# RC_Transmitter_RX_FINAL_v4_4.net
KiCad netlist of a schematic drawn in EAGLE
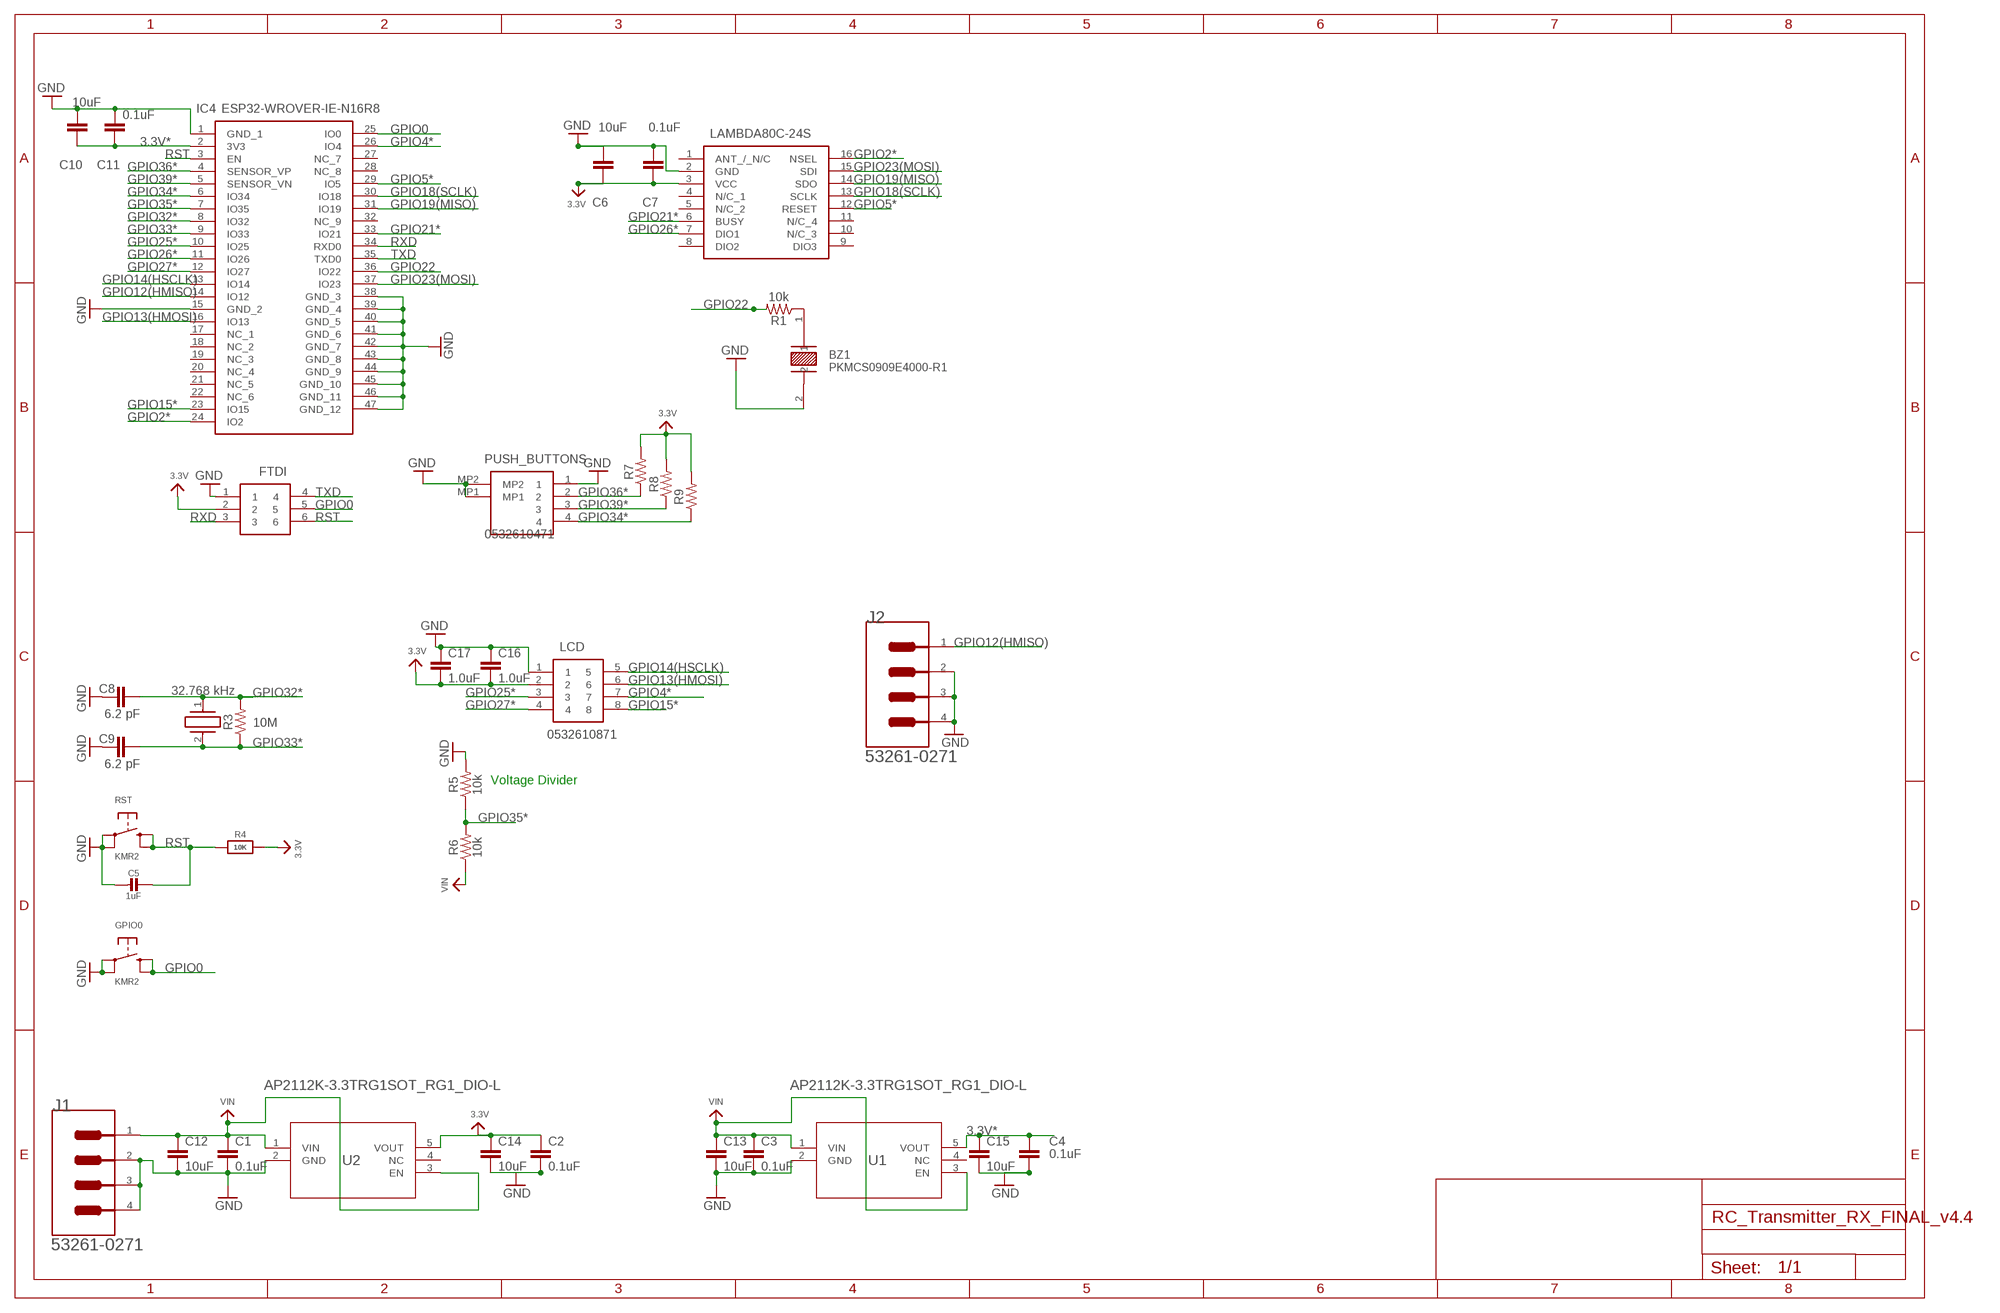
[diagram p0: schematic, sheet 1]

(export (version "E")
  (design (tool "Eeschema 10.0.6"))
  (components
    (comp (ref "BZ1")
      (value "PKMCS0909E4000-R1")
      (footprint "eagle-import:PKMCS0909E4000-R1")
      (fields
        (field (name "DIGIKEY_PARTNO") "490-9647-2-ND")
        (field (name "MANUFACTURER") "Murata Electronics")
        (field (name "CREATED_BY") " PCBLayout.com")
      )
      (libsource (lib "eagle-import") (part "PKMCS0909E4000-R1"))
    )
    (comp (ref "C1")
      (value "0.1uF")
      (footprint "eagle-import:0805")
      (libsource (lib "eagle-import") (part "10UF-0805-10V-10%"))
    )
    (comp (ref "C2")
      (value "0.1uF")
      (footprint "eagle-import:0805")
      (libsource (lib "eagle-import") (part "10UF-0805-10V-10%"))
    )
    (comp (ref "C3")
      (value "0.1uF")
      (footprint "eagle-import:0805")
      (libsource (lib "eagle-import") (part "10UF-0805-10V-10%"))
    )
    (comp (ref "C4")
      (value "0.1uF")
      (footprint "eagle-import:0805")
      (libsource (lib "eagle-import") (part "10UF-0805-10V-10%"))
    )
    (comp (ref "C5")
      (value "1uF")
      (footprint "eagle-import:0805-NO")
      (libsource (lib "eagle-import") (part "CAP_CERAMIC0805-NOOUTLINE"))
    )
    (comp (ref "C6")
      (value "10uF")
      (footprint "eagle-import:0805")
      (libsource (lib "eagle-import") (part "10UF-0805-10V-10%"))
    )
    (comp (ref "C7")
      (value "0.1uF")
      (footprint "eagle-import:0805")
      (libsource (lib "eagle-import") (part "10UF-0805-10V-10%"))
    )
    (comp (ref "C8")
      (value "6.2 pF")
      (footprint "eagle-import:CAPC2012X110")
      (libsource (lib "eagle-import") (part "CCHIP-0805(2012-METRIC)_"))
    )
    (comp (ref "C9")
      (value "6.2 pF")
      (footprint "eagle-import:CAPC2012X110")
      (libsource (lib "eagle-import") (part "CCHIP-0805(2012-METRIC)_"))
    )
    (comp (ref "C10")
      (value "10uF")
      (footprint "eagle-import:0805")
      (libsource (lib "eagle-import") (part "10UF-0805-10V-10%"))
    )
    (comp (ref "C11")
      (value "0.1uF")
      (footprint "eagle-import:0805")
      (libsource (lib "eagle-import") (part "10UF-0805-10V-10%"))
    )
    (comp (ref "C12")
      (value "10uF")
      (footprint "eagle-import:0805")
      (libsource (lib "eagle-import") (part "10UF-0805-10V-10%"))
    )
    (comp (ref "C13")
      (value "10uF")
      (footprint "eagle-import:0805")
      (libsource (lib "eagle-import") (part "10UF-0805-10V-10%"))
    )
    (comp (ref "C14")
      (value "10uF")
      (footprint "eagle-import:0805")
      (libsource (lib "eagle-import") (part "10UF-0805-10V-10%"))
    )
    (comp (ref "C15")
      (value "10uF")
      (footprint "eagle-import:0805")
      (libsource (lib "eagle-import") (part "10UF-0805-10V-10%"))
    )
    (comp (ref "C16")
      (value "1.0uF")
      (footprint "eagle-import:0805")
      (libsource (lib "eagle-import") (part "10UF-0805-10V-10%"))
    )
    (comp (ref "C17")
      (value "1.0uF")
      (footprint "eagle-import:0805")
      (libsource (lib "eagle-import") (part "10UF-0805-10V-10%"))
    )
    (comp (ref "CRYSTAL")
      (value "32.768 kHz")
      (footprint "eagle-import:ECX327CDX1293")
      (fields
        (field (name "ARROW_PART_NUMBER") "ECX-.327-CDX-1293")
        (field (name "MOUSER_PART_NUMBER") "520-ECX-.327CDX-1293")
        (field (name "ARROW_PART_NUMBER_1") "Crystal")
      )
      (libsource (lib "eagle-import") (part "ECX-.327-CDX-1293"))
    )
    (comp (ref "FTDI")
      (value "0532610671")
      (footprint "eagle-import:0532610671")
      (libsource (lib "eagle-import") (part "0532610671"))
    )
    (comp (ref "GPIO0")
      (value "KMR2")
      (footprint "eagle-import:BTN_KMR2_4.6X2.8")
      (libsource (lib "eagle-import") (part "SWITCH_TACT_SMT4.6X2.8"))
    )
    (comp (ref "IC1")
      (value "LAMBDA80C-24S")
      (footprint "eagle-import:LAMBDA80C24S")
      (fields (field (name "MOUSER_PART_NUMBER") "223-LAMBDA80C-24S"))
      (libsource (lib "eagle-import") (part "LAMBDA80C-24S"))
    )
    (comp (ref "IC4")
      (value "ESP32-WROVER-IE-N16R8")
      (footprint "eagle-import:ESP32WROVERIEN16R8")
      (fields
        (field (name "MANUFACTURER_PART_NUMBER") "ESP32-Wrover-IE-N16R8")
        (field (name "MOUSER_PART_NUMBER") "356-ESP32WRVIE2864UC")
      )
      (libsource (lib "eagle-import") (part "ESP32-WROVER-IE-N16R8"))
    )
    (comp (ref "J1")
      (value "MOLEX_53261-0271MOLEX_53261-0271_0_0")
      (footprint "eagle-import:MOLEX_53261-0271_0")
      (fields
        (field (name "DIGIKEY_PART_NUMBER") "WM7620CT-ND")
        (field (name "MF") "Molex")
        (field (name "MOUSER_PART_NUMBER") "538-53261-0271")
      )
      (libsource (lib "eagle-import") (part "MOLEX_53261-0271MOLEX_53261-0271_0_0"))
    )
    (comp (ref "J2")
      (value "MOLEX_53261-0271MOLEX_53261-0271_0_0")
      (footprint "eagle-import:MOLEX_53261-0271_0")
      (fields
        (field (name "DIGIKEY_PART_NUMBER") "WM7620CT-ND")
        (field (name "MF") "Molex")
        (field (name "MOUSER_PART_NUMBER") "538-53261-0271")
      )
      (libsource (lib "eagle-import") (part "MOLEX_53261-0271MOLEX_53261-0271_0_0"))
    )
    (comp (ref "LCD")
      (value "0532610871")
      (footprint "eagle-import:53261-0871")
      (libsource (lib "eagle-import") (part "0532610871"))
    )
    (comp (ref "PUSH_BUTTONS")
      (value "0532610471")
      (footprint "eagle-import:0532610471")
      (libsource (lib "eagle-import") (part "0532610471"))
    )
    (comp (ref "R1")
      (value "10k")
      (footprint "eagle-import:0603")
      (libsource (lib "eagle-import") (part "0OHM-0603-1/10W-5%"))
    )
    (comp (ref "R3")
      (value "10M")
      (footprint "eagle-import:0603")
      (libsource (lib "eagle-import") (part "0OHM-0603-1/10W-5%"))
    )
    (comp (ref "R4")
      (value "10K")
      (footprint "eagle-import:_0805")
      (libsource (lib "eagle-import") (part "RESISTOR_0805"))
    )
    (comp (ref "R5")
      (value "10k")
      (footprint "eagle-import:0603")
      (libsource (lib "eagle-import") (part "0OHM-0603-1/10W-5%"))
    )
    (comp (ref "R6")
      (value "10k")
      (footprint "eagle-import:0603")
      (libsource (lib "eagle-import") (part "0OHM-0603-1/10W-5%"))
    )
    (comp (ref "R7")
      (value "0")
      (footprint "eagle-import:0603")
      (libsource (lib "eagle-import") (part "0OHM-0603-1/10W-5%"))
    )
    (comp (ref "R8")
      (value "0")
      (footprint "eagle-import:0603")
      (libsource (lib "eagle-import") (part "0OHM-0603-1/10W-5%"))
    )
    (comp (ref "R9")
      (value "0")
      (footprint "eagle-import:0603")
      (libsource (lib "eagle-import") (part "0OHM-0603-1/10W-5%"))
    )
    (comp (ref "RST")
      (value "KMR2")
      (footprint "eagle-import:BTN_KMR2_4.6X2.8")
      (libsource (lib "eagle-import") (part "SWITCH_TACT_SMT4.6X2.8"))
    )
    (comp (ref "U1")
      (value "AP2112K-3.3TRG1SOT_RG1_DIO-L")
      (footprint "eagle-import:SOT_RG1_DIO-L")
      (fields
        (field (name "MANUFACTURER_PART_NUMBER") "AP2112K-3.3TRG1")
        (field (name "COPYRIGHT") "Copyright (C) 2023 Ultra Librarian. All rights reserved.")
      )
      (libsource (lib "eagle-import") (part "AP2112K-3.3TRG1SOT_RG1_DIO-L"))
    )
    (comp (ref "U2")
      (value "AP2112K-3.3TRG1SOT_RG1_DIO-L")
      (footprint "eagle-import:SOT_RG1_DIO-L")
      (fields
        (field (name "MANUFACTURER_PART_NUMBER") "AP2112K-3.3TRG1")
        (field (name "COPYRIGHT") "Copyright (C) 2023 Ultra Librarian. All rights reserved.")
      )
      (libsource (lib "eagle-import") (part "AP2112K-3.3TRG1SOT_RG1_DIO-L"))
    )
  )
  (nets
    (net (code "1") (name "/3.3V*") (class "Default")
      (node (ref "C10") (pin "1") (pinfunction "1_1") (pintype "passive"))
      (node (ref "C11") (pin "1") (pinfunction "1_1") (pintype "passive"))
      (node (ref "C15") (pin "1") (pinfunction "1_1") (pintype "passive"))
      (node (ref "C4") (pin "1") (pinfunction "1_1") (pintype "passive"))
      (node (ref "IC4") (pin "2") (pinfunction "3V3_2") (pintype "bidirectional"))
      (node (ref "U1") (pin "5") (pinfunction "VOUT_5") (pintype "passive"))
    )
    (net (code "2") (name "/GPIO0") (class "Default")
      (node (ref "FTDI") (pin "5") (pinfunction "5_5") (pintype "bidirectional"))
      (node (ref "GPIO0") (pin "B") (pinfunction "S_B") (pintype "passive"))
      (node (ref "GPIO0") (pin "B'") (pinfunction "S1_B'") (pintype "passive"))
      (node (ref "IC4") (pin "25") (pinfunction "IO0_25") (pintype "bidirectional"))
    )
    (net (code "3") (name "/GPIO2*") (class "Default")
      (node (ref "IC1") (pin "16") (pinfunction "NSEL_16") (pintype "bidirectional"))
      (node (ref "IC4") (pin "24") (pinfunction "IO2_24") (pintype "bidirectional"))
    )
    (net (code "4") (name "/GPIO4*") (class "Default")
      (node (ref "IC4") (pin "26") (pinfunction "IO4_26") (pintype "bidirectional"))
      (node (ref "LCD") (pin "7") (pinfunction "7_7") (pintype "bidirectional"))
    )
    (net (code "5") (name "/GPIO5*") (class "Default")
      (node (ref "IC1") (pin "12") (pinfunction "RESET_12") (pintype "bidirectional"))
      (node (ref "IC4") (pin "29") (pinfunction "IO5_29") (pintype "bidirectional"))
    )
    (net (code "6") (name "/GPIO12(HMISO)") (class "Default")
      (node (ref "IC4") (pin "14") (pinfunction "IO12_14") (pintype "bidirectional"))
      (node (ref "J2") (pin "1") (pinfunction "1_1") (pintype "bidirectional"))
    )
    (net (code "7") (name "/GPIO13(HMOSI)") (class "Default")
      (node (ref "IC4") (pin "16") (pinfunction "IO13_16") (pintype "bidirectional"))
      (node (ref "LCD") (pin "6") (pinfunction "6_6") (pintype "bidirectional"))
    )
    (net (code "8") (name "/GPIO14(HSCLK)") (class "Default")
      (node (ref "IC4") (pin "13") (pinfunction "IO14_13") (pintype "bidirectional"))
      (node (ref "LCD") (pin "5") (pinfunction "5_5") (pintype "bidirectional"))
    )
    (net (code "9") (name "/GPIO15*") (class "Default")
      (node (ref "IC4") (pin "23") (pinfunction "IO15_23") (pintype "bidirectional"))
      (node (ref "LCD") (pin "8") (pinfunction "8_8") (pintype "bidirectional"))
    )
    (net (code "10") (name "/GPIO18(SCLK)") (class "Default")
      (node (ref "IC1") (pin "13") (pinfunction "SCLK_13") (pintype "bidirectional"))
      (node (ref "IC4") (pin "30") (pinfunction "IO18_30") (pintype "bidirectional"))
    )
    (net (code "11") (name "/GPIO19(MISO)") (class "Default")
      (node (ref "IC1") (pin "14") (pinfunction "SDO_14") (pintype "bidirectional"))
      (node (ref "IC4") (pin "31") (pinfunction "IO19_31") (pintype "bidirectional"))
    )
    (net (code "12") (name "/GPIO21*") (class "Default")
      (node (ref "IC1") (pin "6") (pinfunction "BUSY_6") (pintype "bidirectional"))
      (node (ref "IC4") (pin "33") (pinfunction "IO21_33") (pintype "bidirectional"))
    )
    (net (code "13") (name "/GPIO22") (class "Default")
      (node (ref "IC4") (pin "36") (pinfunction "IO22_36") (pintype "bidirectional"))
      (node (ref "R1") (pin "2") (pinfunction "2_2") (pintype "passive"))
    )
    (net (code "14") (name "/GPIO23(MOSI)") (class "Default")
      (node (ref "IC1") (pin "15") (pinfunction "SDI_15") (pintype "bidirectional"))
      (node (ref "IC4") (pin "37") (pinfunction "IO23_37") (pintype "bidirectional"))
    )
    (net (code "15") (name "/GPIO25*") (class "Default")
      (node (ref "IC4") (pin "10") (pinfunction "IO25_10") (pintype "bidirectional"))
      (node (ref "LCD") (pin "3") (pinfunction "3_3") (pintype "bidirectional"))
    )
    (net (code "16") (name "/GPIO26*") (class "Default")
      (node (ref "IC1") (pin "7") (pinfunction "DIO1_7") (pintype "bidirectional"))
      (node (ref "IC4") (pin "11") (pinfunction "IO26_11") (pintype "bidirectional"))
    )
    (net (code "17") (name "/GPIO27*") (class "Default")
      (node (ref "IC4") (pin "12") (pinfunction "IO27_12") (pintype "bidirectional"))
      (node (ref "LCD") (pin "4") (pinfunction "4_4") (pintype "bidirectional"))
    )
    (net (code "18") (name "/GPIO32*") (class "Default")
      (node (ref "C8") (pin "2") (pinfunction "2_2") (pintype "passive"))
      (node (ref "CRYSTAL") (pin "1") (pinfunction "X1_1") (pintype "bidirectional"))
      (node (ref "IC4") (pin "8") (pinfunction "IO32_8") (pintype "bidirectional"))
      (node (ref "R3") (pin "2") (pinfunction "2_2") (pintype "passive"))
    )
    (net (code "19") (name "/GPIO33*") (class "Default")
      (node (ref "C9") (pin "2") (pinfunction "2_2") (pintype "passive"))
      (node (ref "CRYSTAL") (pin "2") (pinfunction "X2_2") (pintype "bidirectional"))
      (node (ref "IC4") (pin "9") (pinfunction "IO33_9") (pintype "bidirectional"))
      (node (ref "R3") (pin "1") (pinfunction "1_1") (pintype "passive"))
    )
    (net (code "20") (name "/GPIO34*") (class "Default")
      (node (ref "IC4") (pin "6") (pinfunction "IO34_6") (pintype "bidirectional"))
      (node (ref "PUSH_BUTTONS") (pin "4") (pinfunction "4_4") (pintype "bidirectional"))
      (node (ref "R9") (pin "1") (pinfunction "1_1") (pintype "passive"))
    )
    (net (code "21") (name "/GPIO35*") (class "Default")
      (node (ref "IC4") (pin "7") (pinfunction "IO35_7") (pintype "bidirectional"))
      (node (ref "R5") (pin "1") (pinfunction "1_1") (pintype "passive"))
      (node (ref "R6") (pin "2") (pinfunction "2_2") (pintype "passive"))
    )
    (net (code "22") (name "/GPIO36*") (class "Default")
      (node (ref "IC4") (pin "4") (pinfunction "SENSOR_VP_4") (pintype "bidirectional"))
      (node (ref "PUSH_BUTTONS") (pin "2") (pinfunction "2_2") (pintype "bidirectional"))
      (node (ref "R7") (pin "1") (pinfunction "1_1") (pintype "passive"))
    )
    (net (code "23") (name "/GPIO39*") (class "Default")
      (node (ref "IC4") (pin "5") (pinfunction "SENSOR_VN_5") (pintype "bidirectional"))
      (node (ref "PUSH_BUTTONS") (pin "3") (pinfunction "3_3") (pintype "bidirectional"))
      (node (ref "R8") (pin "1") (pinfunction "1_1") (pintype "passive"))
    )
    (net (code "24") (name "/RST") (class "Default")
      (node (ref "C5") (pin "1") (pinfunction "1_1") (pintype "passive"))
      (node (ref "FTDI") (pin "6") (pinfunction "6_6") (pintype "bidirectional"))
      (node (ref "IC4") (pin "3") (pinfunction "EN_3") (pintype "bidirectional"))
      (node (ref "R4") (pin "1") (pinfunction "1_1") (pintype "passive"))
      (node (ref "RST") (pin "B") (pinfunction "S_B") (pintype "passive"))
      (node (ref "RST") (pin "B'") (pinfunction "S1_B'") (pintype "passive"))
    )
    (net (code "25") (name "/RXD") (class "Default")
      (node (ref "FTDI") (pin "3") (pinfunction "3_3") (pintype "bidirectional"))
      (node (ref "IC4") (pin "34") (pinfunction "RXD0_34") (pintype "bidirectional"))
    )
    (net (code "26") (name "/TXD") (class "Default")
      (node (ref "FTDI") (pin "4") (pinfunction "4_4") (pintype "bidirectional"))
      (node (ref "IC4") (pin "35") (pinfunction "TXD0_35") (pintype "bidirectional"))
    )
    (net (code "27") (name "3.3V") (class "Default")
      (node (ref "C14") (pin "1") (pinfunction "1_1") (pintype "passive"))
      (node (ref "C16") (pin "2") (pinfunction "2_2") (pintype "passive"))
      (node (ref "C17") (pin "2") (pinfunction "2_2") (pintype "passive"))
      (node (ref "C2") (pin "1") (pinfunction "1_1") (pintype "passive"))
      (node (ref "C6") (pin "1") (pinfunction "1_1") (pintype "passive"))
      (node (ref "C7") (pin "1") (pinfunction "1_1") (pintype "passive"))
      (node (ref "FTDI") (pin "2") (pinfunction "2_2") (pintype "bidirectional"))
      (node (ref "IC1") (pin "3") (pinfunction "VCC_3") (pintype "bidirectional"))
      (node (ref "LCD") (pin "2") (pinfunction "2_2") (pintype "bidirectional"))
      (node (ref "R4") (pin "2") (pinfunction "2_2") (pintype "passive"))
      (node (ref "R7") (pin "2") (pinfunction "2_2") (pintype "passive"))
      (node (ref "R8") (pin "2") (pinfunction "2_2") (pintype "passive"))
      (node (ref "R9") (pin "2") (pinfunction "2_2") (pintype "passive"))
      (node (ref "U2") (pin "5") (pinfunction "VOUT_5") (pintype "passive"))
    )
    (net (code "28") (name "GND") (class "Default")
      (node (ref "BZ1") (pin "2") (pinfunction "2_2") (pintype "passive"))
      (node (ref "C1") (pin "2") (pinfunction "2_2") (pintype "passive"))
      (node (ref "C10") (pin "2") (pinfunction "2_2") (pintype "passive"))
      (node (ref "C11") (pin "2") (pinfunction "2_2") (pintype "passive"))
      (node (ref "C12") (pin "2") (pinfunction "2_2") (pintype "passive"))
      (node (ref "C13") (pin "2") (pinfunction "2_2") (pintype "passive"))
      (node (ref "C14") (pin "2") (pinfunction "2_2") (pintype "passive"))
      (node (ref "C15") (pin "2") (pinfunction "2_2") (pintype "passive"))
      (node (ref "C16") (pin "1") (pinfunction "1_1") (pintype "passive"))
      (node (ref "C17") (pin "1") (pinfunction "1_1") (pintype "passive"))
      (node (ref "C2") (pin "2") (pinfunction "2_2") (pintype "passive"))
      (node (ref "C3") (pin "2") (pinfunction "2_2") (pintype "passive"))
      (node (ref "C4") (pin "2") (pinfunction "2_2") (pintype "passive"))
      (node (ref "C5") (pin "2") (pinfunction "2_2") (pintype "passive"))
      (node (ref "C6") (pin "2") (pinfunction "2_2") (pintype "passive"))
      (node (ref "C7") (pin "2") (pinfunction "2_2") (pintype "passive"))
      (node (ref "C8") (pin "1") (pinfunction "1_1") (pintype "passive"))
      (node (ref "C9") (pin "1") (pinfunction "1_1") (pintype "passive"))
      (node (ref "FTDI") (pin "1") (pinfunction "1_1") (pintype "bidirectional"))
      (node (ref "GPIO0") (pin "A") (pinfunction "P_A") (pintype "passive"))
      (node (ref "GPIO0") (pin "A'") (pinfunction "P1_A'") (pintype "passive"))
      (node (ref "IC1") (pin "2") (pinfunction "GND_2") (pintype "bidirectional"))
      (node (ref "IC4") (pin "1") (pinfunction "GND_1_1") (pintype "bidirectional"))
      (node (ref "IC4") (pin "15") (pinfunction "GND_2_15") (pintype "bidirectional"))
      (node (ref "IC4") (pin "38") (pinfunction "GND_3_38") (pintype "bidirectional"))
      (node (ref "IC4") (pin "39") (pinfunction "GND_4_39") (pintype "bidirectional"))
      (node (ref "IC4") (pin "40") (pinfunction "GND_5_40") (pintype "bidirectional"))
      (node (ref "IC4") (pin "41") (pinfunction "GND_6_41") (pintype "bidirectional"))
      (node (ref "IC4") (pin "42") (pinfunction "GND_7_42") (pintype "bidirectional"))
      (node (ref "IC4") (pin "43") (pinfunction "GND_8_43") (pintype "bidirectional"))
      (node (ref "IC4") (pin "44") (pinfunction "GND_9_44") (pintype "bidirectional"))
      (node (ref "IC4") (pin "45") (pinfunction "GND_10_45") (pintype "bidirectional"))
      (node (ref "IC4") (pin "46") (pinfunction "GND_11_46") (pintype "bidirectional"))
      (node (ref "IC4") (pin "47") (pinfunction "GND_12_47") (pintype "bidirectional"))
      (node (ref "J1") (pin "2") (pinfunction "2_2") (pintype "bidirectional"))
      (node (ref "J1") (pin "3") (pinfunction "MNT_1_3") (pintype "bidirectional"))
      (node (ref "J1") (pin "4") (pinfunction "MNT_2_4") (pintype "bidirectional"))
      (node (ref "J2") (pin "2") (pinfunction "2_2") (pintype "bidirectional"))
      (node (ref "J2") (pin "3") (pinfunction "MNT_1_3") (pintype "bidirectional"))
      (node (ref "J2") (pin "4") (pinfunction "MNT_2_4") (pintype "bidirectional"))
      (node (ref "LCD") (pin "1") (pinfunction "1_1") (pintype "bidirectional"))
      (node (ref "PUSH_BUTTONS") (pin "1") (pinfunction "1_1") (pintype "bidirectional"))
      (node (ref "PUSH_BUTTONS") (pin "MP1") (pinfunction "MP1_MP1") (pintype "bidirectional"))
      (node (ref "PUSH_BUTTONS") (pin "MP2") (pinfunction "MP2_MP2") (pintype "bidirectional"))
      (node (ref "R5") (pin "2") (pinfunction "2_2") (pintype "passive"))
      (node (ref "RST") (pin "A") (pinfunction "P_A") (pintype "passive"))
      (node (ref "RST") (pin "A'") (pinfunction "P1_A'") (pintype "passive"))
      (node (ref "U1") (pin "2") (pinfunction "GND_2") (pintype "passive"))
      (node (ref "U2") (pin "2") (pinfunction "GND_2") (pintype "passive"))
    )
    (net (code "29") (name "Net-(BZ1-Pad1)") (class "Default")
      (node (ref "BZ1") (pin "1") (pinfunction "1_1") (pintype "passive"))
      (node (ref "R1") (pin "1") (pinfunction "1_1") (pintype "passive"))
    )
    (net (code "30") (name "VIN") (class "Default")
      (node (ref "C1") (pin "1") (pinfunction "1_1") (pintype "passive"))
      (node (ref "C12") (pin "1") (pinfunction "1_1") (pintype "passive"))
      (node (ref "C13") (pin "1") (pinfunction "1_1") (pintype "passive"))
      (node (ref "C3") (pin "1") (pinfunction "1_1") (pintype "passive"))
      (node (ref "J1") (pin "1") (pinfunction "1_1") (pintype "bidirectional"))
      (node (ref "R6") (pin "1") (pinfunction "1_1") (pintype "passive"))
      (node (ref "U1") (pin "1") (pinfunction "VIN_1") (pintype "passive"))
      (node (ref "U1") (pin "3") (pinfunction "EN_3") (pintype "passive"))
      (node (ref "U2") (pin "1") (pinfunction "VIN_1") (pintype "passive"))
      (node (ref "U2") (pin "3") (pinfunction "EN_3") (pintype "passive"))
    )
    (net (code "31") (name "unconnected-(IC1-ANT_{slash}_N{slash}C-Pad1)") (class "Default")
      (node (ref "IC1") (pin "1") (pinfunction "ANT_/_N/C_1") (pintype "bidirectional"))
    )
    (net (code "32") (name "unconnected-(IC1-DIO2-Pad8)") (class "Default")
      (node (ref "IC1") (pin "8") (pinfunction "DIO2_8") (pintype "bidirectional"))
    )
    (net (code "33") (name "unconnected-(IC1-DIO3-Pad9)") (class "Default")
      (node (ref "IC1") (pin "9") (pinfunction "DIO3_9") (pintype "bidirectional"))
    )
    (net (code "34") (name "unconnected-(IC1-N{slash}C_1-Pad4)") (class "Default")
      (node (ref "IC1") (pin "4") (pinfunction "N/C_1_4") (pintype "bidirectional"))
    )
    (net (code "35") (name "unconnected-(IC1-N{slash}C_2-Pad5)") (class "Default")
      (node (ref "IC1") (pin "5") (pinfunction "N/C_2_5") (pintype "bidirectional"))
    )
    (net (code "36") (name "unconnected-(IC1-N{slash}C_3-Pad10)") (class "Default")
      (node (ref "IC1") (pin "10") (pinfunction "N/C_3_10") (pintype "bidirectional"))
    )
    (net (code "37") (name "unconnected-(IC1-N{slash}C_4-Pad11)") (class "Default")
      (node (ref "IC1") (pin "11") (pinfunction "N/C_4_11") (pintype "bidirectional"))
    )
    (net (code "38") (name "unconnected-(IC4-NC_1-Pad17)") (class "Default")
      (node (ref "IC4") (pin "17") (pinfunction "NC_1_17") (pintype "bidirectional"))
    )
    (net (code "39") (name "unconnected-(IC4-NC_2-Pad18)") (class "Default")
      (node (ref "IC4") (pin "18") (pinfunction "NC_2_18") (pintype "bidirectional"))
    )
    (net (code "40") (name "unconnected-(IC4-NC_3-Pad19)") (class "Default")
      (node (ref "IC4") (pin "19") (pinfunction "NC_3_19") (pintype "bidirectional"))
    )
    (net (code "41") (name "unconnected-(IC4-NC_4-Pad20)") (class "Default")
      (node (ref "IC4") (pin "20") (pinfunction "NC_4_20") (pintype "bidirectional"))
    )
    (net (code "42") (name "unconnected-(IC4-NC_5-Pad21)") (class "Default")
      (node (ref "IC4") (pin "21") (pinfunction "NC_5_21") (pintype "bidirectional"))
    )
    (net (code "43") (name "unconnected-(IC4-NC_6-Pad22)") (class "Default")
      (node (ref "IC4") (pin "22") (pinfunction "NC_6_22") (pintype "bidirectional"))
    )
    (net (code "44") (name "unconnected-(IC4-NC_7-Pad27)") (class "Default")
      (node (ref "IC4") (pin "27") (pinfunction "NC_7_27") (pintype "bidirectional"))
    )
    (net (code "45") (name "unconnected-(IC4-NC_8-Pad28)") (class "Default")
      (node (ref "IC4") (pin "28") (pinfunction "NC_8_28") (pintype "bidirectional"))
    )
    (net (code "46") (name "unconnected-(IC4-NC_9-Pad32)") (class "Default")
      (node (ref "IC4") (pin "32") (pinfunction "NC_9_32") (pintype "bidirectional"))
    )
    (net (code "47") (name "unconnected-(U1-NC-Pad4)") (class "Default")
      (node (ref "U1") (pin "4") (pinfunction "NC_4") (pintype "passive"))
    )
    (net (code "48") (name "unconnected-(U2-NC-Pad4)") (class "Default")
      (node (ref "U2") (pin "4") (pinfunction "NC_4") (pintype "passive"))
    )
  )
)
